# sqrwear-mini.net
KiCad netlist of a schematic drawn in EAGLE
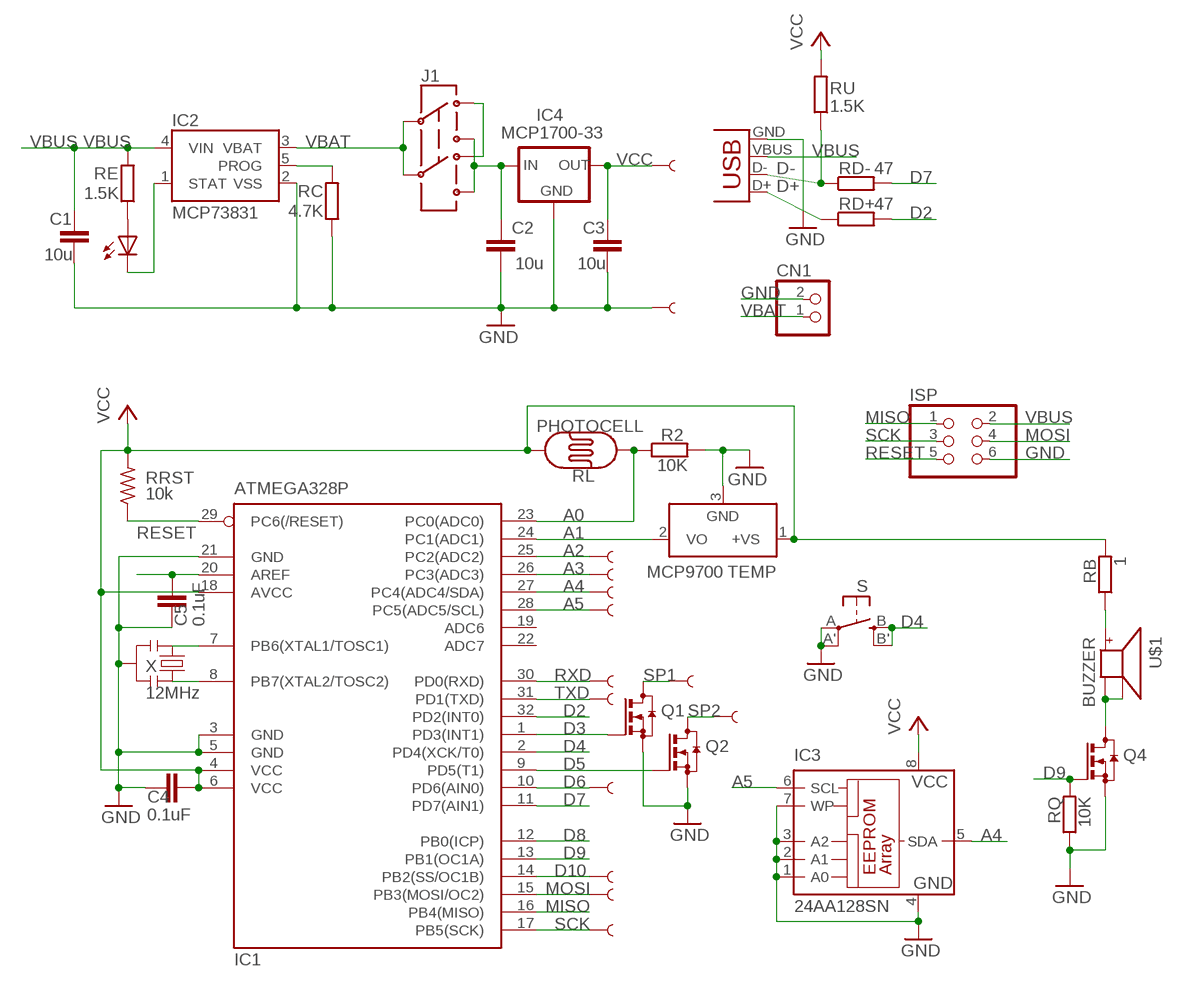
[diagram p0: schematic, sheet 1]

(export (version "E")
  (design (tool "Eeschema 10.0.6"))
  (components
    (comp (ref "C1")
      (value "10u")
      (footprint "eagle-import:C0805K")
      (libsource (lib "eagle-import") (part "resistor_C-EUC0805K"))
    )
    (comp (ref "C2")
      (value "10u")
      (footprint "eagle-import:C0805K")
      (libsource (lib "eagle-import") (part "resistor_C-EUC0805K"))
    )
    (comp (ref "C3")
      (value "10u")
      (footprint "eagle-import:C0805K")
      (libsource (lib "eagle-import") (part "resistor_C-EUC0805K"))
    )
    (comp (ref "C4")
      (value "0.1uF")
      (footprint "eagle-import:C0805K")
      (libsource (lib "eagle-import") (part "C-EUC0805K"))
    )
    (comp (ref "C5")
      (value "0.1uF")
      (footprint "eagle-import:C0805K")
      (libsource (lib "eagle-import") (part "C-EUC0805K"))
    )
    (comp (ref "CHG")
      (value "0805")
      (footprint "eagle-import:CHIPLED_0805")
      (libsource (lib "eagle-import") (part "LEDCHIPLED_0805"))
    )
    (comp (ref "CN1")
      (value "JST_2PIN-SMT-RA")
      (footprint "eagle-import:JST-PH-2-SMT-RA")
      (libsource (lib "eagle-import") (part "JST_2PIN-SMT-RA"))
    )
    (comp (ref "IC1")
      (value "ATMEGA328P")
      (footprint "eagle-import:TQFP32-08")
      (fields (field (name "MPN") "ATMEGA8-16AU"))
      (libsource (lib "eagle-import") (part "MEGA8-AI"))
    )
    (comp (ref "IC2")
      (value "MCP73831")
      (footprint "eagle-import:SOT23-5")
      (libsource (lib "eagle-import") (part "MCP73831"))
    )
    (comp (ref "IC3")
      (value "24AA128SN")
      (footprint "eagle-import:SO-08")
      (fields (field (name "MF") "MICROCHIP") (field (name "MPN") "24AA128-I/SN"))
      (libsource (lib "eagle-import") (part "24SNAA128"))
    )
    (comp (ref "IC4")
      (value "MCP1700-33")
      (footprint "eagle-import:SOT23")
      (libsource (lib "eagle-import") (part "MCP1700SOT233"))
    )
    (comp (ref "ISP")
      (value "PINHD-2X3")
      (footprint "eagle-import:2X03")
      (libsource (lib "eagle-import") (part "PINHD-2X3"))
    )
    (comp (ref "J1")
      (value "AYZ0202")
      (footprint "eagle-import:AYZ0202")
      (libsource (lib "eagle-import") (part "AYZ0202"))
    )
    (comp (ref "PAD_3")
      (value "SEWTAP6")
      (footprint "eagle-import:PETAL-SMALL-2SIDE11")
      (libsource (lib "eagle-import") (part "SEWTAP611"))
    )
    (comp (ref "PAD_5")
      (value "SEWTAP6")
      (footprint "eagle-import:PETAL-SMALL-2SIDE1")
      (libsource (lib "eagle-import") (part "SEWTAP61"))
    )
    (comp (ref "PAD_6")
      (value "SEWTAP6")
      (footprint "eagle-import:PETAL-SMALL-2SIDE1")
      (libsource (lib "eagle-import") (part "SEWTAP61"))
    )
    (comp (ref "PAD_10")
      (value "SEWTAP6")
      (footprint "eagle-import:PETAL-SMALL-2SIDE11")
      (libsource (lib "eagle-import") (part "SEWTAP611"))
    )
    (comp (ref "PAD_11")
      (value "SEWTAP6")
      (footprint "eagle-import:PETAL-SMALL-2SIDE1")
      (libsource (lib "eagle-import") (part "SEWTAP61"))
    )
    (comp (ref "PAD_13")
      (value "SEWTAP6")
      (footprint "eagle-import:PETAL-SMALL-2SIDE1")
      (libsource (lib "eagle-import") (part "SEWTAP61"))
    )
    (comp (ref "PAD_A2")
      (value "SEWTAP6")
      (footprint "eagle-import:PETAL-SMALL-2SIDE1")
      (libsource (lib "eagle-import") (part "SEWTAP61"))
    )
    (comp (ref "PAD_A3")
      (value "SEWTAP6")
      (footprint "eagle-import:PETAL-SMALL-2SIDE1")
      (libsource (lib "eagle-import") (part "SEWTAP61"))
    )
    (comp (ref "PAD_A4")
      (value "SEWTAP6")
      (footprint "eagle-import:PETAL-SMALL-2SIDE11")
      (libsource (lib "eagle-import") (part "SEWTAP611"))
    )
    (comp (ref "PAD_A5")
      (value "SEWTAP6")
      (footprint "eagle-import:PETAL-SMALL-2SIDE11")
      (libsource (lib "eagle-import") (part "SEWTAP611"))
    )
    (comp (ref "PAD_GND")
      (value "SEWTAP6")
      (footprint "eagle-import:PETAL-SMALL-2SIDE11")
      (libsource (lib "eagle-import") (part "SEWTAP611"))
    )
    (comp (ref "PAD_RXD")
      (value "SEWTAP61")
      (footprint "eagle-import:PETAL-SMALL-2SIDE1")
      (libsource (lib "eagle-import") (part "SEWTAP61"))
    )
    (comp (ref "PAD_TXD")
      (value "SEWTAP6")
      (footprint "eagle-import:PETAL-SMALL-2SIDE1")
      (libsource (lib "eagle-import") (part "SEWTAP61"))
    )
    (comp (ref "PAD_VCC")
      (value "SEWTAP6")
      (footprint "eagle-import:PETAL-SMALL-2SIDE11")
      (libsource (lib "eagle-import") (part "SEWTAP611"))
    )
    (comp (ref "Q1")
      (value "BSS123")
      (footprint "eagle-import:SOT23")
      (libsource (lib "eagle-import") (part "BSS123"))
    )
    (comp (ref "Q2")
      (value "BSS123")
      (footprint "eagle-import:SOT23")
      (libsource (lib "eagle-import") (part "BSS123"))
    )
    (comp (ref "Q4")
      (value "BSS123")
      (footprint "eagle-import:SOT23")
      (libsource (lib "eagle-import") (part "BSS123"))
    )
    (comp (ref "R2")
      (value "10K")
      (footprint "eagle-import:R0805")
      (libsource (lib "eagle-import") (part "R-EU_R0805"))
    )
    (comp (ref "RB")
      (value "1")
      (footprint "eagle-import:R0805")
      (libsource (lib "eagle-import") (part "R-EU_R0805"))
    )
    (comp (ref "RC")
      (value "4.7K")
      (footprint "eagle-import:R0805")
      (libsource (lib "eagle-import") (part "R-EU_R0805"))
    )
    (comp (ref "RD+")
      (value "47")
      (footprint "eagle-import:R0805")
      (libsource (lib "eagle-import") (part "R-EU_R0805"))
    )
    (comp (ref "RD-")
      (value "47")
      (footprint "eagle-import:R0805")
      (libsource (lib "eagle-import") (part "R-EU_R0805"))
    )
    (comp (ref "RE")
      (value "1.5K")
      (footprint "eagle-import:R0805")
      (libsource (lib "eagle-import") (part "R-EU_R0805"))
    )
    (comp (ref "RL")
      (value "PHOTOCELL")
      (footprint "eagle-import:PHOTOCELL")
      (libsource (lib "eagle-import") (part "PHOTOCELLPTH"))
    )
    (comp (ref "RQ")
      (value "10K")
      (footprint "eagle-import:R0805")
      (libsource (lib "eagle-import") (part "R-EU_R0805"))
    )
    (comp (ref "RRST")
      (value "10k")
      (footprint "eagle-import:R0805")
      (libsource (lib "eagle-import") (part "R-US_R0805"))
    )
    (comp (ref "RU")
      (value "1.5K")
      (footprint "eagle-import:R0805")
      (libsource (lib "eagle-import") (part "R-EU_R0805"))
    )
    (comp (ref "S")
      (value "EVQQ2")
      (footprint "eagle-import:EVQ-Q2")
      (libsource (lib "eagle-import") (part "EVQQ2"))
    )
    (comp (ref "TEMP")
      (value "MCP9700")
      (footprint "eagle-import:SOT23")
      (libsource (lib "eagle-import") (part "LM50"))
    )
    (comp (ref "U$1")
      (value "BUZZER")
      (footprint "eagle-import:SMT-8585-BUZZER")
      (libsource (lib "eagle-import") (part "BUZZER"))
    )
    (comp (ref "X")
      (value "12MHz")
      (footprint "eagle-import:RESONATOR-SMD")
      (libsource (lib "eagle-import") (part "RESONATORSMD"))
    )
    (comp (ref "X1")
      (value "USBSMD")
      (footprint "eagle-import:USB-MINIB")
      (libsource (lib "eagle-import") (part "USBSMD"))
    )
  )
  (nets
    (net (code "1") (name "/A0") (class "Default")
      (node (ref "IC1") (pin "23") (pinfunction "PC0(ADC0)_23") (pintype "bidirectional"))
      (node (ref "R2") (pin "1") (pinfunction "1_1") (pintype "passive"))
      (node (ref "RL") (pin "1") (pinfunction "P$1_1") (pintype "bidirectional"))
    )
    (net (code "2") (name "/A1") (class "Default")
      (node (ref "IC1") (pin "24") (pinfunction "PC1(ADC1)_24") (pintype "bidirectional"))
      (node (ref "TEMP") (pin "2") (pinfunction "VO_2") (pintype "input"))
    )
    (net (code "3") (name "/A2") (class "Default")
      (node (ref "IC1") (pin "25") (pinfunction "PC2(ADC2)_25") (pintype "bidirectional"))
      (node (ref "PAD_A2") (pin "1") (pinfunction "1_1") (pintype "bidirectional"))
    )
    (net (code "4") (name "/A3") (class "Default")
      (node (ref "IC1") (pin "26") (pinfunction "PC3(ADC3)_26") (pintype "bidirectional"))
      (node (ref "PAD_A3") (pin "1") (pinfunction "1_1") (pintype "bidirectional"))
    )
    (net (code "5") (name "/A4") (class "Default")
      (node (ref "IC1") (pin "27") (pinfunction "PC4(ADC4/SDA)_27") (pintype "bidirectional"))
      (node (ref "IC3") (pin "5") (pinfunction "SDA_5") (pintype "bidirectional"))
      (node (ref "PAD_A4") (pin "1") (pinfunction "1_1") (pintype "bidirectional"))
    )
    (net (code "6") (name "/A5") (class "Default")
      (node (ref "IC1") (pin "28") (pinfunction "PC5(ADC5/SCL)_28") (pintype "bidirectional"))
      (node (ref "IC3") (pin "6") (pinfunction "SCL_6") (pintype "input"))
      (node (ref "PAD_A5") (pin "1") (pinfunction "1_1") (pintype "bidirectional"))
    )
    (net (code "7") (name "/D+") (class "Default")
      (node (ref "RD+") (pin "1") (pinfunction "1_1") (pintype "passive"))
      (node (ref "X1") (pin "D+") (pinfunction "D+_D+") (pintype "bidirectional"))
    )
    (net (code "8") (name "/D-") (class "Default")
      (node (ref "RD-") (pin "1") (pinfunction "1_1") (pintype "passive"))
      (node (ref "RU") (pin "1") (pinfunction "1_1") (pintype "passive"))
      (node (ref "X1") (pin "D-") (pinfunction "D-_D-") (pintype "bidirectional"))
    )
    (net (code "9") (name "/D2") (class "Default")
      (node (ref "IC1") (pin "32") (pinfunction "PD2(INT0)_32") (pintype "bidirectional"))
      (node (ref "RD+") (pin "2") (pinfunction "2_2") (pintype "passive"))
    )
    (net (code "10") (name "/D3") (class "Default")
      (node (ref "IC1") (pin "1") (pinfunction "PD3(INT1)_1") (pintype "bidirectional"))
      (node (ref "Q1") (pin "1") (pinfunction "G_1") (pintype "passive"))
    )
    (net (code "11") (name "/D4") (class "Default")
      (node (ref "IC1") (pin "2") (pinfunction "PD4(XCK/T0)_2") (pintype "bidirectional"))
      (node (ref "S") (pin "B") (pinfunction "S_B") (pintype "passive"))
      (node (ref "S") (pin "B'") (pinfunction "S1_B'") (pintype "passive"))
    )
    (net (code "12") (name "/D5") (class "Default")
      (node (ref "IC1") (pin "9") (pinfunction "PD5(T1)_9") (pintype "bidirectional"))
      (node (ref "Q2") (pin "1") (pinfunction "G_1") (pintype "passive"))
    )
    (net (code "13") (name "/D6") (class "Default")
      (node (ref "IC1") (pin "10") (pinfunction "PD6(AIN0)_10") (pintype "bidirectional"))
      (node (ref "PAD_6") (pin "1") (pinfunction "1_1") (pintype "bidirectional"))
    )
    (net (code "14") (name "/D7") (class "Default")
      (node (ref "IC1") (pin "11") (pinfunction "PD7(AIN1)_11") (pintype "bidirectional"))
      (node (ref "RD-") (pin "2") (pinfunction "2_2") (pintype "passive"))
    )
    (net (code "15") (name "/D8") (class "Default")
      (node (ref "IC1") (pin "12") (pinfunction "PB0(ICP)_12") (pintype "bidirectional"))
    )
    (net (code "16") (name "/D9") (class "Default")
      (node (ref "IC1") (pin "13") (pinfunction "PB1(OC1A)_13") (pintype "bidirectional"))
      (node (ref "Q4") (pin "1") (pinfunction "G_1") (pintype "passive"))
      (node (ref "RQ") (pin "2") (pinfunction "2_2") (pintype "passive"))
    )
    (net (code "17") (name "/D10") (class "Default")
      (node (ref "IC1") (pin "14") (pinfunction "PB2(SS/OC1B)_14") (pintype "bidirectional"))
      (node (ref "PAD_10") (pin "1") (pinfunction "1_1") (pintype "bidirectional"))
    )
    (net (code "18") (name "/MISO") (class "Default")
      (node (ref "IC1") (pin "16") (pinfunction "PB4(MISO)_16") (pintype "bidirectional"))
      (node (ref "ISP") (pin "1") (pinfunction "1_1") (pintype "passive"))
    )
    (net (code "19") (name "/MOSI") (class "Default")
      (node (ref "IC1") (pin "15") (pinfunction "PB3(MOSI/OC2)_15") (pintype "bidirectional"))
      (node (ref "ISP") (pin "4") (pinfunction "4_4") (pintype "passive"))
      (node (ref "PAD_11") (pin "1") (pinfunction "1_1") (pintype "bidirectional"))
    )
    (net (code "20") (name "/RESET") (class "Default")
      (node (ref "IC1") (pin "29") (pinfunction "PC6(/RESET)_29") (pintype "bidirectional"))
      (node (ref "ISP") (pin "5") (pinfunction "5_5") (pintype "passive"))
      (node (ref "RRST") (pin "1") (pinfunction "1_1") (pintype "passive"))
    )
    (net (code "21") (name "/RXD") (class "Default")
      (node (ref "IC1") (pin "30") (pinfunction "PD0(RXD)_30") (pintype "bidirectional"))
      (node (ref "PAD_RXD") (pin "1") (pinfunction "1_1") (pintype "bidirectional"))
    )
    (net (code "22") (name "/SCK") (class "Default")
      (node (ref "IC1") (pin "17") (pinfunction "PB5(SCK)_17") (pintype "bidirectional"))
      (node (ref "ISP") (pin "3") (pinfunction "3_3") (pintype "passive"))
      (node (ref "PAD_13") (pin "1") (pinfunction "1_1") (pintype "bidirectional"))
    )
    (net (code "23") (name "/SP1") (class "Default")
      (node (ref "PAD_3") (pin "1") (pinfunction "1_1") (pintype "bidirectional"))
      (node (ref "Q1") (pin "3") (pinfunction "D_3") (pintype "passive"))
    )
    (net (code "24") (name "/SP2") (class "Default")
      (node (ref "PAD_5") (pin "1") (pinfunction "1_1") (pintype "bidirectional"))
      (node (ref "Q2") (pin "3") (pinfunction "D_3") (pintype "passive"))
    )
    (net (code "25") (name "/TXD") (class "Default")
      (node (ref "IC1") (pin "31") (pinfunction "PD1(TXD)_31") (pintype "bidirectional"))
      (node (ref "PAD_TXD") (pin "1") (pinfunction "1_1") (pintype "bidirectional"))
    )
    (net (code "26") (name "/VBAT") (class "Default")
      (node (ref "CN1") (pin "1") (pinfunction "2_1") (pintype "passive"))
      (node (ref "IC2") (pin "3") (pinfunction "VBAT_3") (pintype "power_in"))
      (node (ref "J1") (pin "2") (pinfunction "2_2") (pintype "bidirectional"))
      (node (ref "J1") (pin "5") (pinfunction "5_5") (pintype "bidirectional"))
    )
    (net (code "27") (name "/VBUS") (class "Default")
      (node (ref "C1") (pin "1") (pinfunction "1_1") (pintype "passive"))
      (node (ref "IC2") (pin "4") (pinfunction "VIN_4") (pintype "power_in"))
      (node (ref "ISP") (pin "2") (pinfunction "2_2") (pintype "passive"))
      (node (ref "RE") (pin "2") (pinfunction "2_2") (pintype "passive"))
      (node (ref "X1") (pin "VBUS") (pinfunction "VBUS_VBUS") (pintype "bidirectional"))
    )
    (net (code "28") (name "GND") (class "Default")
      (node (ref "C1") (pin "2") (pinfunction "2_2") (pintype "passive"))
      (node (ref "C2") (pin "2") (pinfunction "2_2") (pintype "passive"))
      (node (ref "C3") (pin "2") (pinfunction "2_2") (pintype "passive"))
      (node (ref "C4") (pin "1") (pinfunction "1_1") (pintype "passive"))
      (node (ref "C5") (pin "1") (pinfunction "1_1") (pintype "passive"))
      (node (ref "CN1") (pin "2") (pinfunction "1_2") (pintype "passive"))
      (node (ref "IC1") (pin "21") (pinfunction "GND_21") (pintype "power_in"))
      (node (ref "IC1") (pin "3") (pinfunction "GND_3") (pintype "power_in"))
      (node (ref "IC1") (pin "5") (pinfunction "GND_5") (pintype "power_in"))
      (node (ref "IC2") (pin "2") (pinfunction "VSS_2") (pintype "power_in"))
      (node (ref "IC3") (pin "1") (pinfunction "A0_1") (pintype "input"))
      (node (ref "IC3") (pin "2") (pinfunction "A1_2") (pintype "input"))
      (node (ref "IC3") (pin "3") (pinfunction "A2_3") (pintype "input"))
      (node (ref "IC3") (pin "4") (pinfunction "GND_4") (pintype "power_in"))
      (node (ref "IC3") (pin "7") (pinfunction "WP_7") (pintype "input"))
      (node (ref "IC4") (pin "1") (pinfunction "GND_1") (pintype "input"))
      (node (ref "ISP") (pin "6") (pinfunction "6_6") (pintype "passive"))
      (node (ref "PAD_GND") (pin "1") (pinfunction "1_1") (pintype "bidirectional"))
      (node (ref "Q1") (pin "2") (pinfunction "S_2") (pintype "passive"))
      (node (ref "Q2") (pin "2") (pinfunction "S_2") (pintype "passive"))
      (node (ref "Q4") (pin "2") (pinfunction "S_2") (pintype "passive"))
      (node (ref "R2") (pin "2") (pinfunction "2_2") (pintype "passive"))
      (node (ref "RC") (pin "1") (pinfunction "1_1") (pintype "passive"))
      (node (ref "RQ") (pin "1") (pinfunction "1_1") (pintype "passive"))
      (node (ref "S") (pin "A") (pinfunction "P_A") (pintype "passive"))
      (node (ref "S") (pin "A'") (pinfunction "P1_A'") (pintype "passive"))
      (node (ref "TEMP") (pin "3") (pinfunction "GND_3") (pintype "power_in"))
      (node (ref "X") (pin "2") (pinfunction "2_2") (pintype "passive"))
      (node (ref "X1") (pin "GND") (pinfunction "GND_GND") (pintype "bidirectional"))
    )
    (net (code "29") (name "Net-(CHG-PadA)") (class "Default")
      (node (ref "CHG") (pin "A") (pinfunction "A_A") (pintype "passive"))
      (node (ref "RE") (pin "1") (pinfunction "1_1") (pintype "passive"))
    )
    (net (code "30") (name "Net-(IC1-AREF)") (class "Default")
      (node (ref "C5") (pin "2") (pinfunction "2_2") (pintype "passive"))
      (node (ref "IC1") (pin "20") (pinfunction "AREF_20") (pintype "passive"))
    )
    (net (code "31") (name "Net-(IC1-PB6(XTAL1{slash}TOSC1))") (class "Default")
      (node (ref "IC1") (pin "7") (pinfunction "PB6(XTAL1/TOSC1)_7") (pintype "bidirectional"))
      (node (ref "X") (pin "1") (pinfunction "1_1") (pintype "passive"))
    )
    (net (code "32") (name "Net-(IC1-PB7(XTAL2{slash}TOSC2))") (class "Default")
      (node (ref "IC1") (pin "8") (pinfunction "PB7(XTAL2/TOSC2)_8") (pintype "bidirectional"))
      (node (ref "X") (pin "3") (pinfunction "3_3") (pintype "passive"))
    )
    (net (code "33") (name "Net-(IC2-PROG)") (class "Default")
      (node (ref "IC2") (pin "5") (pinfunction "PROG_5") (pintype "input"))
      (node (ref "RC") (pin "2") (pinfunction "2_2") (pintype "passive"))
    )
    (net (code "34") (name "Net-(IC2-STAT)") (class "Default")
      (node (ref "CHG") (pin "C") (pinfunction "C_C") (pintype "passive"))
      (node (ref "IC2") (pin "1") (pinfunction "STAT_1") (pintype "output"))
    )
    (net (code "35") (name "Net-(IC4-IN)") (class "Default")
      (node (ref "C2") (pin "1") (pinfunction "1_1") (pintype "passive"))
      (node (ref "IC4") (pin "3") (pinfunction "IN_3") (pintype "input"))
      (node (ref "J1") (pin "1") (pinfunction "3_1") (pintype "bidirectional"))
      (node (ref "J1") (pin "4") (pinfunction "6_4") (pintype "bidirectional"))
    )
    (net (code "36") (name "Net-(J1-1)") (class "Default")
      (node (ref "J1") (pin "3") (pinfunction "1_3") (pintype "bidirectional"))
      (node (ref "J1") (pin "6") (pinfunction "4_6") (pintype "bidirectional"))
    )
    (net (code "37") (name "Net-(Q4-D)") (class "Default")
      (node (ref "Q4") (pin "3") (pinfunction "D_3") (pintype "passive"))
      (node (ref "U$1") (pin "-") (pinfunction "-_-") (pintype "passive"))
      (node (ref "U$1") (pin "A-") (pinfunction "A-_A-") (pintype "passive"))
    )
    (net (code "38") (name "Net-(RB-Pad1)") (class "Default")
      (node (ref "RB") (pin "1") (pinfunction "1_1") (pintype "passive"))
      (node (ref "U$1") (pin "+") (pinfunction "+_+") (pintype "passive"))
    )
    (net (code "39") (name "VCC") (class "Default")
      (node (ref "C3") (pin "1") (pinfunction "1_1") (pintype "passive"))
      (node (ref "C4") (pin "2") (pinfunction "2_2") (pintype "passive"))
      (node (ref "IC1") (pin "18") (pinfunction "AVCC_18") (pintype "power_in"))
      (node (ref "IC1") (pin "4") (pinfunction "VCC_4") (pintype "power_in"))
      (node (ref "IC1") (pin "6") (pinfunction "VCC_6") (pintype "power_in"))
      (node (ref "IC3") (pin "8") (pinfunction "VCC_8") (pintype "power_in"))
      (node (ref "IC4") (pin "2") (pinfunction "OUT_2") (pintype "passive"))
      (node (ref "PAD_VCC") (pin "1") (pinfunction "1_1") (pintype "bidirectional"))
      (node (ref "RB") (pin "2") (pinfunction "2_2") (pintype "passive"))
      (node (ref "RL") (pin "2") (pinfunction "P$2_2") (pintype "bidirectional"))
      (node (ref "RRST") (pin "2") (pinfunction "2_2") (pintype "passive"))
      (node (ref "RU") (pin "2") (pinfunction "2_2") (pintype "passive"))
      (node (ref "TEMP") (pin "1") (pinfunction "+VS_1") (pintype "input"))
    )
    (net (code "40") (name "unconnected-(IC1-ADC6-Pad19)") (class "Default")
      (node (ref "IC1") (pin "19") (pinfunction "ADC6_19") (pintype "bidirectional"))
    )
    (net (code "41") (name "unconnected-(IC1-ADC7-Pad22)") (class "Default")
      (node (ref "IC1") (pin "22") (pinfunction "ADC7_22") (pintype "bidirectional"))
    )
  )
)
